# left_switch_module.net
KiCad netlist of a schematic drawn in EAGLE
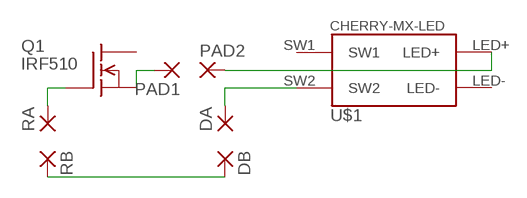
[diagram p0: schematic, sheet 1]

(export (version "E")
  (design (tool "Eeschema 10.0.6"))
  (components
    (comp (ref "DA")
      (value "2,15/1,0")
      (footprint "eagle-import:2,15_1,0")
      (libsource (lib "eagle-import") (part "2,15/1,0"))
    )
    (comp (ref "DB")
      (value "2,15/1,0")
      (footprint "eagle-import:2,15_1,0")
      (libsource (lib "eagle-import") (part "2,15/1,0"))
    )
    (comp (ref "PAD1")
      (value "1,6/0,9")
      (footprint "eagle-import:1,6_0,9")
      (libsource (lib "eagle-import") (part "1,6/0,9"))
    )
    (comp (ref "PAD2")
      (value "1,6/0,9")
      (footprint "eagle-import:1,6_0,9")
      (libsource (lib "eagle-import") (part "1,6/0,9"))
    )
    (comp (ref "Q1")
      (value "IRF510")
      (footprint "eagle-import:TO220")
      (libsource (lib "eagle-import") (part "IRF510"))
    )
    (comp (ref "RA")
      (value "2,15/1,0")
      (footprint "eagle-import:2,15_1,0")
      (libsource (lib "eagle-import") (part "2,15/1,0"))
    )
    (comp (ref "RB")
      (value "2,15/1,0")
      (footprint "eagle-import:2,15_1,0")
      (libsource (lib "eagle-import") (part "2,15/1,0"))
    )
    (comp (ref "U$1")
      (value "CHERRY-MX-LED")
      (footprint "eagle-import:CHERRY-MX-LED")
      (libsource (lib "eagle-import") (part "CHERRY-MX-LED"))
    )
  )
  (nets
    (net (code "1") (name "Net-(DA-P)") (class "Default")
      (node (ref "DA") (pin "1") (pinfunction "P_1") (pintype "passive"))
      (node (ref "U$1") (pin "SW2") (pinfunction "SW2_SW2") (pintype "bidirectional"))
    )
    (net (code "2") (name "Net-(DB-P)") (class "Default")
      (node (ref "DB") (pin "1") (pinfunction "P_1") (pintype "passive"))
      (node (ref "RB") (pin "1") (pinfunction "P_1") (pintype "passive"))
    )
    (net (code "3") (name "Net-(PAD1-P)") (class "Default")
      (node (ref "PAD1") (pin "1") (pinfunction "P_1") (pintype "passive"))
      (node (ref "Q1") (pin "3") (pinfunction "S_3") (pintype "passive"))
    )
    (net (code "4") (name "Net-(PAD2-P)") (class "Default")
      (node (ref "PAD2") (pin "1") (pinfunction "P_1") (pintype "passive"))
      (node (ref "U$1") (pin "LED+") (pinfunction "LED+_LED+") (pintype "bidirectional"))
    )
    (net (code "5") (name "Net-(Q1-G)") (class "Default")
      (node (ref "Q1") (pin "1") (pinfunction "G_1") (pintype "passive"))
      (node (ref "RA") (pin "1") (pinfunction "P_1") (pintype "passive"))
    )
    (net (code "6") (name "unconnected-(Q1-D-Pad2)") (class "Default")
      (node (ref "Q1") (pin "2") (pinfunction "D_2") (pintype "passive"))
    )
    (net (code "7") (name "unconnected-(U$1-PadLED-)") (class "Default")
      (node (ref "U$1") (pin "LED-") (pinfunction "LED-_LED-") (pintype "bidirectional"))
    )
    (net (code "8") (name "unconnected-(U$1-PadSW1)") (class "Default")
      (node (ref "U$1") (pin "SW1") (pinfunction "SW1_SW1") (pintype "bidirectional"))
    )
  )
)
